# 7971DoubleDriver.net
KiCad netlist of a schematic drawn in Altium Designer
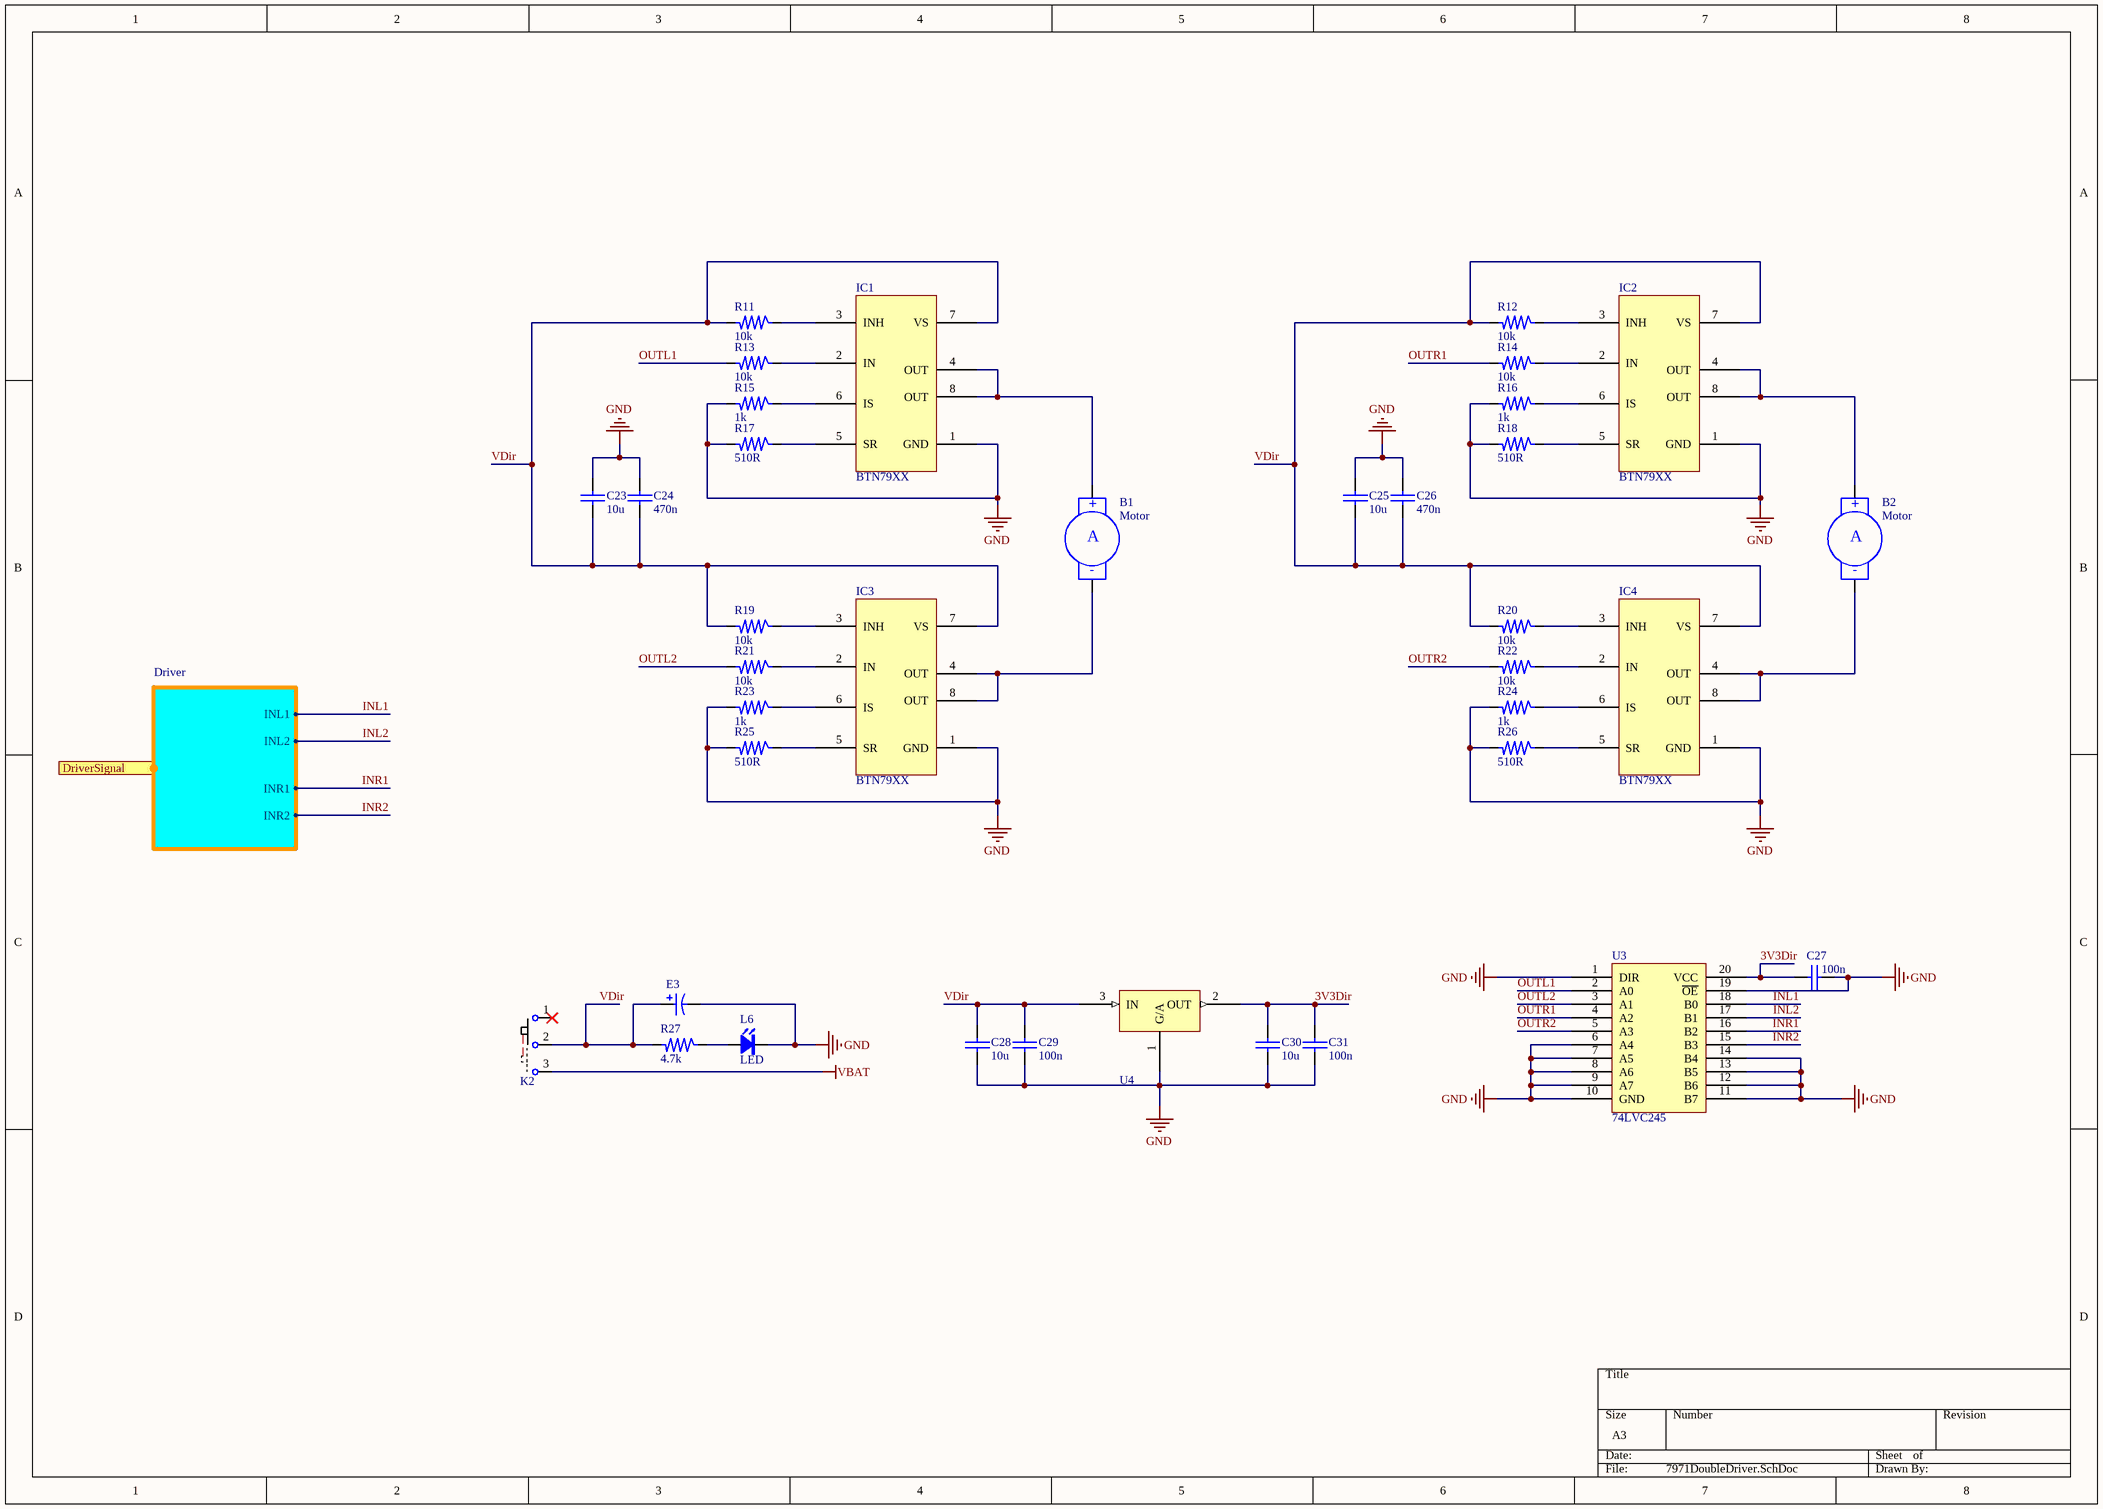
[diagram p0: 7971DoubleDriver.SchDoc]

(export (version "E")
  (design (tool "Eeschema 10.0.6"))
  (components
    (comp (ref "B1")
      (value "Motor")
      (footprint "KF301-2P")
      (description "Servo Motor")
      (libsource (lib "LQ_Integrated_Library") (part "Motor Servo"))
    )
    (comp (ref "B2")
      (value "Motor")
      (footprint "KF301-2P")
      (description "Servo Motor")
      (libsource (lib "LQ_Integrated_Library") (part "Motor Servo"))
    )
    (comp (ref "C23")
      (value "10u")
      (footprint "C0805")
      (description "电容")
      (libsource (lib "LQ_Integrated_Library") (part "Capacitor"))
    )
    (comp (ref "C24")
      (value "470n")
      (footprint "C0603")
      (description "电容")
      (libsource (lib "LQ_Integrated_Library") (part "Capacitor"))
    )
    (comp (ref "C25")
      (value "10u")
      (footprint "C0805")
      (description "电容")
      (libsource (lib "LQ_Integrated_Library") (part "Capacitor"))
    )
    (comp (ref "C26")
      (value "470n")
      (footprint "C0603")
      (description "电容")
      (libsource (lib "LQ_Integrated_Library") (part "Capacitor"))
    )
    (comp (ref "C27")
      (value "100n")
      (footprint "C0603")
      (description "电容")
      (libsource (lib "LQ_Integrated_Library") (part "Capacitor"))
    )
    (comp (ref "C28")
      (value "10u")
      (footprint "C0805")
      (description "电容")
      (libsource (lib "LQ_Integrated_Library") (part "Capacitor"))
    )
    (comp (ref "C29")
      (value "100n")
      (footprint "C0603")
      (description "电容")
      (libsource (lib "LQ_Integrated_Library") (part "Capacitor"))
    )
    (comp (ref "C30")
      (value "10u")
      (footprint "C0805")
      (description "电容")
      (libsource (lib "LQ_Integrated_Library") (part "Capacitor"))
    )
    (comp (ref "C31")
      (value "100n")
      (footprint "C0603")
      (description "电容")
      (libsource (lib "LQ_Integrated_Library") (part "Capacitor"))
    )
    (comp (ref "E3")
      (value "100u")
      (footprint "CAP-E SMD-D")
      (description "极性电容")
      (libsource (lib "LQ_Integrated_Library") (part "Capacitor-Polarity"))
    )
    (comp (ref "IC1")
      (value "BTN79XX")
      (footprint "PG-TO263-7-1")
      (description "BTN7960/7971/799X")
      (libsource (lib "LQ_Integrated_Library") (part "BTN79XX"))
    )
    (comp (ref "IC2")
      (value "BTN79XX")
      (footprint "PG-TO263-7-1")
      (description "BTN7960/7971/799X")
      (libsource (lib "LQ_Integrated_Library") (part "BTN79XX"))
    )
    (comp (ref "IC3")
      (value "BTN79XX")
      (footprint "PG-TO263-7-1")
      (description "BTN7960/7971/799X")
      (libsource (lib "LQ_Integrated_Library") (part "BTN79XX"))
    )
    (comp (ref "IC4")
      (value "BTN79XX")
      (footprint "PG-TO263-7-1")
      (description "BTN7960/7971/799X")
      (libsource (lib "LQ_Integrated_Library") (part "BTN79XX"))
    )
    (comp (ref "K2")
      (value "RES-SEL")
      (footprint "NIUZI_SWITCH")
      (description "扭子开关")
      (libsource (lib "LQ_Integrated_Library") (part "RES-SEL"))
    )
    (comp (ref "L6")
      (value "LED")
      (footprint "LED0805TB")
      (libsource (lib "LQ_Integrated_Library") (part "LED"))
    )
    (comp (ref "R11")
      (value "10k")
      (footprint "R0603")
      (description "电阻")
      (libsource (lib "LQ_Integrated_Library") (part "Resistor"))
    )
    (comp (ref "R12")
      (value "10k")
      (footprint "R0603")
      (description "电阻")
      (libsource (lib "LQ_Integrated_Library") (part "Resistor"))
    )
    (comp (ref "R13")
      (value "10k")
      (footprint "R0603")
      (description "电阻")
      (libsource (lib "LQ_Integrated_Library") (part "Resistor"))
    )
    (comp (ref "R14")
      (value "10k")
      (footprint "R0603")
      (description "电阻")
      (libsource (lib "LQ_Integrated_Library") (part "Resistor"))
    )
    (comp (ref "R15")
      (value "1k")
      (footprint "R0603")
      (description "电阻")
      (libsource (lib "LQ_Integrated_Library") (part "Resistor"))
    )
    (comp (ref "R16")
      (value "1k")
      (footprint "R0603")
      (description "电阻")
      (libsource (lib "LQ_Integrated_Library") (part "Resistor"))
    )
    (comp (ref "R17")
      (value "510R")
      (footprint "R0603")
      (description "电阻")
      (libsource (lib "LQ_Integrated_Library") (part "Resistor"))
    )
    (comp (ref "R18")
      (value "510R")
      (footprint "R0603")
      (description "电阻")
      (libsource (lib "LQ_Integrated_Library") (part "Resistor"))
    )
    (comp (ref "R19")
      (value "10k")
      (footprint "R0603")
      (description "电阻")
      (libsource (lib "LQ_Integrated_Library") (part "Resistor"))
    )
    (comp (ref "R20")
      (value "10k")
      (footprint "R0603")
      (description "电阻")
      (libsource (lib "LQ_Integrated_Library") (part "Resistor"))
    )
    (comp (ref "R21")
      (value "10k")
      (footprint "R0603")
      (description "电阻")
      (libsource (lib "LQ_Integrated_Library") (part "Resistor"))
    )
    (comp (ref "R22")
      (value "10k")
      (footprint "R0603")
      (description "电阻")
      (libsource (lib "LQ_Integrated_Library") (part "Resistor"))
    )
    (comp (ref "R23")
      (value "1k")
      (footprint "R0603")
      (description "电阻")
      (libsource (lib "LQ_Integrated_Library") (part "Resistor"))
    )
    (comp (ref "R24")
      (value "1k")
      (footprint "R0603")
      (description "电阻")
      (libsource (lib "LQ_Integrated_Library") (part "Resistor"))
    )
    (comp (ref "R25")
      (value "510R")
      (footprint "R0603")
      (description "电阻")
      (libsource (lib "LQ_Integrated_Library") (part "Resistor"))
    )
    (comp (ref "R26")
      (value "510R")
      (footprint "R0603")
      (description "电阻")
      (libsource (lib "LQ_Integrated_Library") (part "Resistor"))
    )
    (comp (ref "R27")
      (value "4.7k")
      (footprint "R0603")
      (description "电阻")
      (libsource (lib "LQ_Integrated_Library") (part "Resistor"))
    )
    (comp (ref "U3")
      (value "74LVC245")
      (footprint "TSSOP20")
      (description "8位5伏转3.3伏电平转换芯片")
      (libsource (lib "LQ_Integrated_Library") (part "74lvc245"))
    )
    (comp (ref "U4")
      (value "AMS1117-XX")
      (footprint "SOT223")
      (description "稳压芯片")
      (libsource (lib "LQ_Integrated_Library") (part "AMS1117-XX"))
    )
  )
  (nets
    (net (code "2") (name "/3V3Dir") (class "Default")
      (node (ref "C27") (pin "1") (pinfunction "1_1") (pintype "passive"))
      (node (ref "C30") (pin "1") (pinfunction "1_1") (pintype "passive"))
      (node (ref "C31") (pin "1") (pinfunction "1_1") (pintype "passive"))
      (node (ref "U3") (pin "20") (pinfunction "VCC_20") (pintype "passive"))
      (node (ref "U4") (pin "2") (pinfunction "OUT_2") (pintype "output"))
    )
    (net (code "3") (name "/INL1") (class "Default")
      (node (ref "U3") (pin "18") (pinfunction "B0_18") (pintype "passive"))
    )
    (net (code "4") (name "/INL2") (class "Default")
      (node (ref "U3") (pin "17") (pinfunction "B1_17") (pintype "passive"))
    )
    (net (code "5") (name "/INR1") (class "Default")
      (node (ref "U3") (pin "16") (pinfunction "B2_16") (pintype "passive"))
    )
    (net (code "6") (name "/INR2") (class "Default")
      (node (ref "U3") (pin "15") (pinfunction "B3_15") (pintype "passive"))
    )
    (net (code "7") (name "/OUTL1") (class "Default")
      (node (ref "R13") (pin "1") (pinfunction "1_1") (pintype "passive"))
      (node (ref "U3") (pin "2") (pinfunction "A0_2") (pintype "passive"))
    )
    (net (code "8") (name "/OUTL2") (class "Default")
      (node (ref "R21") (pin "1") (pinfunction "1_1") (pintype "passive"))
      (node (ref "U3") (pin "3") (pinfunction "A1_3") (pintype "passive"))
    )
    (net (code "9") (name "/OUTR1") (class "Default")
      (node (ref "R14") (pin "1") (pinfunction "1_1") (pintype "passive"))
      (node (ref "U3") (pin "4") (pinfunction "A2_4") (pintype "passive"))
    )
    (net (code "10") (name "/OUTR2") (class "Default")
      (node (ref "R22") (pin "1") (pinfunction "1_1") (pintype "passive"))
      (node (ref "U3") (pin "5") (pinfunction "A3_5") (pintype "passive"))
    )
    (net (code "11") (name "/VDir") (class "Default")
      (node (ref "C23") (pin "2") (pinfunction "2_2") (pintype "passive"))
      (node (ref "C24") (pin "1") (pinfunction "1_1") (pintype "passive"))
      (node (ref "C25") (pin "2") (pinfunction "2_2") (pintype "passive"))
      (node (ref "C26") (pin "1") (pinfunction "1_1") (pintype "passive"))
      (node (ref "C28") (pin "1") (pinfunction "1_1") (pintype "passive"))
      (node (ref "C29") (pin "1") (pinfunction "1_1") (pintype "passive"))
      (node (ref "E3") (pin "1") (pinfunction "1_1") (pintype "passive"))
      (node (ref "IC1") (pin "7") (pinfunction "VS_7") (pintype "passive"))
      (node (ref "IC2") (pin "7") (pinfunction "VS_7") (pintype "passive"))
      (node (ref "IC3") (pin "7") (pinfunction "VS_7") (pintype "passive"))
      (node (ref "IC4") (pin "7") (pinfunction "VS_7") (pintype "passive"))
      (node (ref "K2") (pin "2") (pinfunction "2_2") (pintype "passive"))
      (node (ref "R11") (pin "1") (pinfunction "1_1") (pintype "passive"))
      (node (ref "R12") (pin "1") (pinfunction "1_1") (pintype "passive"))
      (node (ref "R19") (pin "1") (pinfunction "1_1") (pintype "passive"))
      (node (ref "R20") (pin "1") (pinfunction "1_1") (pintype "passive"))
      (node (ref "R27") (pin "1") (pinfunction "1_1") (pintype "passive"))
      (node (ref "U4") (pin "3") (pinfunction "IN_3") (pintype "input"))
    )
    (net (code "13") (name "GND") (class "Default")
      (node (ref "C23") (pin "1") (pinfunction "1_1") (pintype "passive"))
      (node (ref "C24") (pin "2") (pinfunction "2_2") (pintype "passive"))
      (node (ref "C25") (pin "1") (pinfunction "1_1") (pintype "passive"))
      (node (ref "C26") (pin "2") (pinfunction "2_2") (pintype "passive"))
      (node (ref "C27") (pin "2") (pinfunction "2_2") (pintype "passive"))
      (node (ref "C28") (pin "2") (pinfunction "2_2") (pintype "passive"))
      (node (ref "C29") (pin "2") (pinfunction "2_2") (pintype "passive"))
      (node (ref "C30") (pin "2") (pinfunction "2_2") (pintype "passive"))
      (node (ref "C31") (pin "2") (pinfunction "2_2") (pintype "passive"))
      (node (ref "E3") (pin "2") (pinfunction "2_2") (pintype "passive"))
      (node (ref "IC1") (pin "1") (pinfunction "GND_1") (pintype "passive"))
      (node (ref "IC2") (pin "1") (pinfunction "GND_1") (pintype "passive"))
      (node (ref "IC3") (pin "1") (pinfunction "GND_1") (pintype "passive"))
      (node (ref "IC4") (pin "1") (pinfunction "GND_1") (pintype "passive"))
      (node (ref "L6") (pin "2") (pinfunction "K_2") (pintype "passive"))
      (node (ref "R15") (pin "1") (pinfunction "1_1") (pintype "passive"))
      (node (ref "R16") (pin "1") (pinfunction "1_1") (pintype "passive"))
      (node (ref "R17") (pin "1") (pinfunction "1_1") (pintype "passive"))
      (node (ref "R18") (pin "1") (pinfunction "1_1") (pintype "passive"))
      (node (ref "R23") (pin "1") (pinfunction "1_1") (pintype "passive"))
      (node (ref "R24") (pin "1") (pinfunction "1_1") (pintype "passive"))
      (node (ref "R25") (pin "1") (pinfunction "1_1") (pintype "passive"))
      (node (ref "R26") (pin "1") (pinfunction "1_1") (pintype "passive"))
      (node (ref "U3") (pin "1") (pinfunction "DIR_1") (pintype "passive"))
      (node (ref "U3") (pin "10") (pinfunction "GND_10") (pintype "passive"))
      (node (ref "U3") (pin "11") (pinfunction "B7_11") (pintype "passive"))
      (node (ref "U3") (pin "12") (pinfunction "B6_12") (pintype "passive"))
      (node (ref "U3") (pin "13") (pinfunction "B5_13") (pintype "passive"))
      (node (ref "U3") (pin "14") (pinfunction "B4_14") (pintype "passive"))
      (node (ref "U3") (pin "19") (pinfunction "~{OE}_19") (pintype "passive"))
      (node (ref "U3") (pin "6") (pinfunction "A4_6") (pintype "passive"))
      (node (ref "U3") (pin "7") (pinfunction "A5_7") (pintype "passive"))
      (node (ref "U3") (pin "8") (pinfunction "A6_8") (pintype "passive"))
      (node (ref "U3") (pin "9") (pinfunction "A7_9") (pintype "passive"))
      (node (ref "U4") (pin "1") (pinfunction "G/A_1") (pintype "passive"))
    )
    (net (code "14") (name "Net-(B1-+)") (class "Default")
      (node (ref "B1") (pin "1") (pinfunction "+_1") (pintype "passive"))
      (node (ref "IC1") (pin "4") (pinfunction "OUT_4") (pintype "passive"))
      (node (ref "IC1") (pin "8") (pinfunction "OUT_8") (pintype "passive"))
    )
    (net (code "15") (name "Net-(B1--)") (class "Default")
      (node (ref "B1") (pin "2") (pinfunction "-_2") (pintype "passive"))
      (node (ref "IC3") (pin "4") (pinfunction "OUT_4") (pintype "passive"))
      (node (ref "IC3") (pin "8") (pinfunction "OUT_8") (pintype "passive"))
    )
    (net (code "16") (name "Net-(B2-+)") (class "Default")
      (node (ref "B2") (pin "1") (pinfunction "+_1") (pintype "passive"))
      (node (ref "IC2") (pin "4") (pinfunction "OUT_4") (pintype "passive"))
      (node (ref "IC2") (pin "8") (pinfunction "OUT_8") (pintype "passive"))
    )
    (net (code "17") (name "Net-(B2--)") (class "Default")
      (node (ref "B2") (pin "2") (pinfunction "-_2") (pintype "passive"))
      (node (ref "IC4") (pin "4") (pinfunction "OUT_4") (pintype "passive"))
      (node (ref "IC4") (pin "8") (pinfunction "OUT_8") (pintype "passive"))
    )
    (net (code "18") (name "Net-(IC1-IN)") (class "Default")
      (node (ref "IC1") (pin "2") (pinfunction "IN_2") (pintype "passive"))
      (node (ref "R13") (pin "2") (pinfunction "2_2") (pintype "passive"))
    )
    (net (code "19") (name "Net-(IC1-INH)") (class "Default")
      (node (ref "IC1") (pin "3") (pinfunction "INH_3") (pintype "passive"))
      (node (ref "R11") (pin "2") (pinfunction "2_2") (pintype "passive"))
    )
    (net (code "20") (name "Net-(IC1-IS)") (class "Default")
      (node (ref "IC1") (pin "6") (pinfunction "IS_6") (pintype "passive"))
      (node (ref "R15") (pin "2") (pinfunction "2_2") (pintype "passive"))
    )
    (net (code "21") (name "Net-(IC1-SR)") (class "Default")
      (node (ref "IC1") (pin "5") (pinfunction "SR_5") (pintype "passive"))
      (node (ref "R17") (pin "2") (pinfunction "2_2") (pintype "passive"))
    )
    (net (code "22") (name "Net-(IC2-IN)") (class "Default")
      (node (ref "IC2") (pin "2") (pinfunction "IN_2") (pintype "passive"))
      (node (ref "R14") (pin "2") (pinfunction "2_2") (pintype "passive"))
    )
    (net (code "23") (name "Net-(IC2-INH)") (class "Default")
      (node (ref "IC2") (pin "3") (pinfunction "INH_3") (pintype "passive"))
      (node (ref "R12") (pin "2") (pinfunction "2_2") (pintype "passive"))
    )
    (net (code "24") (name "Net-(IC2-IS)") (class "Default")
      (node (ref "IC2") (pin "6") (pinfunction "IS_6") (pintype "passive"))
      (node (ref "R16") (pin "2") (pinfunction "2_2") (pintype "passive"))
    )
    (net (code "25") (name "Net-(IC2-SR)") (class "Default")
      (node (ref "IC2") (pin "5") (pinfunction "SR_5") (pintype "passive"))
      (node (ref "R18") (pin "2") (pinfunction "2_2") (pintype "passive"))
    )
    (net (code "26") (name "Net-(IC3-IN)") (class "Default")
      (node (ref "IC3") (pin "2") (pinfunction "IN_2") (pintype "passive"))
      (node (ref "R21") (pin "2") (pinfunction "2_2") (pintype "passive"))
    )
    (net (code "27") (name "Net-(IC3-INH)") (class "Default")
      (node (ref "IC3") (pin "3") (pinfunction "INH_3") (pintype "passive"))
      (node (ref "R19") (pin "2") (pinfunction "2_2") (pintype "passive"))
    )
    (net (code "28") (name "Net-(IC3-IS)") (class "Default")
      (node (ref "IC3") (pin "6") (pinfunction "IS_6") (pintype "passive"))
      (node (ref "R23") (pin "2") (pinfunction "2_2") (pintype "passive"))
    )
    (net (code "29") (name "Net-(IC3-SR)") (class "Default")
      (node (ref "IC3") (pin "5") (pinfunction "SR_5") (pintype "passive"))
      (node (ref "R25") (pin "2") (pinfunction "2_2") (pintype "passive"))
    )
    (net (code "30") (name "Net-(IC4-IN)") (class "Default")
      (node (ref "IC4") (pin "2") (pinfunction "IN_2") (pintype "passive"))
      (node (ref "R22") (pin "2") (pinfunction "2_2") (pintype "passive"))
    )
    (net (code "31") (name "Net-(IC4-INH)") (class "Default")
      (node (ref "IC4") (pin "3") (pinfunction "INH_3") (pintype "passive"))
      (node (ref "R20") (pin "2") (pinfunction "2_2") (pintype "passive"))
    )
    (net (code "32") (name "Net-(IC4-IS)") (class "Default")
      (node (ref "IC4") (pin "6") (pinfunction "IS_6") (pintype "passive"))
      (node (ref "R24") (pin "2") (pinfunction "2_2") (pintype "passive"))
    )
    (net (code "33") (name "Net-(IC4-SR)") (class "Default")
      (node (ref "IC4") (pin "5") (pinfunction "SR_5") (pintype "passive"))
      (node (ref "R26") (pin "2") (pinfunction "2_2") (pintype "passive"))
    )
    (net (code "34") (name "Net-(L6-A)") (class "Default")
      (node (ref "L6") (pin "1") (pinfunction "A_1") (pintype "passive"))
      (node (ref "R27") (pin "2") (pinfunction "2_2") (pintype "passive"))
    )
    (net (code "35") (name "VBAT") (class "Default")
      (node (ref "K2") (pin "3") (pinfunction "3_3") (pintype "passive"))
    )
    (net (code "36") (name "unconnected-(K2-Pad1)") (class "Default")
      (node (ref "K2") (pin "1") (pinfunction "1_1") (pintype "passive+no_connect"))
    )
  )
)
